# 04_Power.net
KiCad netlist of a schematic drawn in Altium Designer
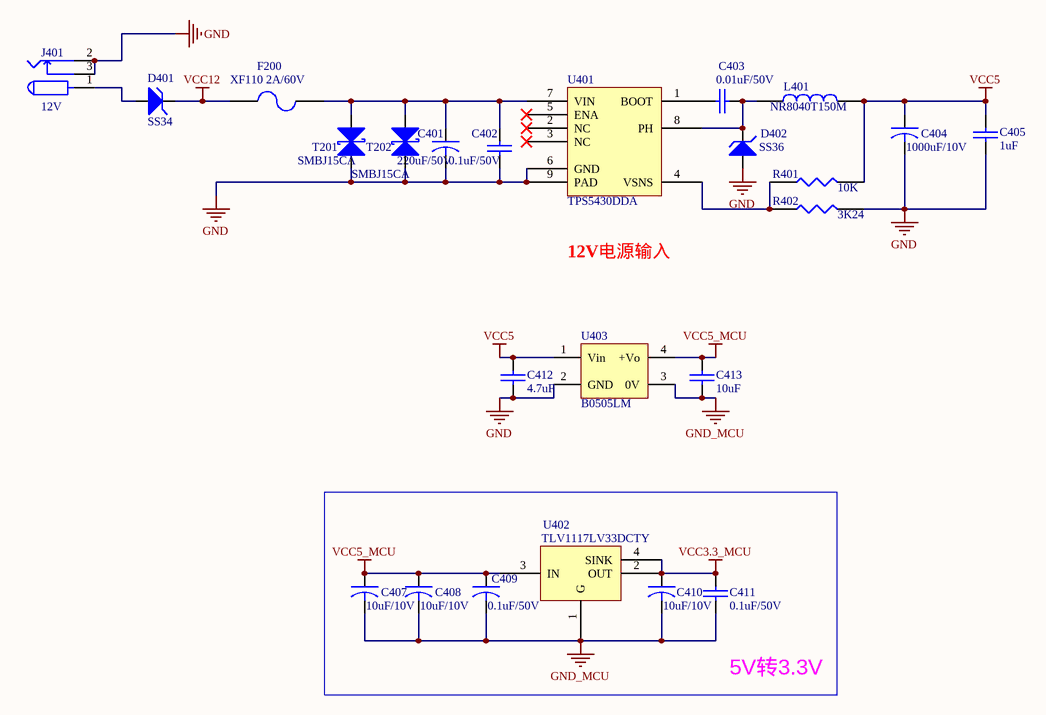
[diagram p0: 04_Power.SchDoc]

(export (version "E")
  (design (tool "Eeschema 10.0.6"))
  (components
    (comp (ref "C401")
      (value "220uF/50V")
      (footprint "CD's_LIB_2018:RB050-100")
      (description "Capacitor")
      (libsource (lib "*") (part "CAPACITOR"))
    )
    (comp (ref "C402")
      (value "0.1uF/50V")
      (footprint "CD's_LIB_2018:0805C")
      (description "Capacitor")
      (libsource (lib "*") (part "CAP"))
    )
    (comp (ref "C403")
      (value "0.01uF/50V")
      (footprint "0603C")
      (description "Capacitor")
      (libsource (lib "*") (part "CAP"))
    )
    (comp (ref "C404")
      (value "1000uF/10V")
      (footprint "RB035-080")
      (description "Capacitor")
      (libsource (lib "*") (part "CAPACITOR"))
    )
    (comp (ref "C405")
      (value "1uF")
      (footprint "0603C")
      (description "Capacitor 0805")
      (libsource (lib "CD's_LIB_2018") (part "0805C"))
    )
    (comp (ref "C407")
      (value "10uF/10V")
      (footprint "0805C")
      (description "Capacitor")
      (libsource (lib "*") (part "CAPACITOR"))
    )
    (comp (ref "C408")
      (value "10uF/10V")
      (footprint "0603C")
      (description "Capacitor")
      (libsource (lib "*") (part "CAPACITOR"))
    )
    (comp (ref "C409")
      (value "0.1uF/50V")
      (footprint "0805C")
      (description "Capacitor")
      (libsource (lib "*") (part "CAPACITOR"))
    )
    (comp (ref "C410")
      (value "10uF/10V")
      (footprint "0805C")
      (description "Capacitor")
      (libsource (lib "*") (part "CAPACITOR"))
    )
    (comp (ref "C411") (value "0.1uF/50V") (footprint "0603C") (libsource (lib "") (part "CAP_1")))
    (comp (ref "C412")
      (value "4.7uF")
      (footprint "0603C")
      (description "Capacitor 0805")
      (libsource (lib "CD's_LIB_2018") (part "0805C"))
    )
    (comp (ref "C413")
      (value "10uF")
      (footprint "0603C")
      (description "Capacitor 0805")
      (libsource (lib "CD's_LIB_2018") (part "0805C"))
    )
    (comp (ref "D401")
      (value "SS34")
      (footprint "D1812")
      (description "Zener Diode")
      (libsource (lib "CD's_LIB_2018") (part "1N5822"))
    )
    (comp (ref "D402")
      (value "SS36")
      (footprint "D1812")
      (description "Zener Diode")
      (libsource (lib "*") (part "SS36"))
    )
    (comp (ref "F200")
      (value "XF110 2A/60V")
      (footprint "FUSE1")
      (description "Fuse")
      (libsource (lib "*") (part "FUSE2"))
    )
    (comp (ref "J401")
      (value "12V")
      (footprint "DC10B")
      (libsource (lib "Explorer STM32F407封装库") (part "POW"))
    )
    (comp (ref "L401") (value "NR8040T150M") (footprint "NR8040") (libsource (lib "*") (part "INDUCTOR")))
    (comp (ref "R401") (value "10K") (footprint "0603R") (libsource (lib "*") (part "RES1")))
    (comp (ref "R402") (value "3K24") (footprint "0603R") (libsource (lib "*") (part "RES1")))
    (comp (ref "T201") (value "SMBJ15CA") (footprint "CD's_LIB_2018:SMBJ") (libsource (lib "*") (part "TVS")))
    (comp (ref "T202") (value "SMBJ15CA") (footprint "CD's_LIB_2018:SMBJ") (libsource (lib "*") (part "TVS")))
    (comp (ref "U401") (value "TPS5430DDA") (footprint "SO-G8") (libsource (lib "*") (part "TPS5430DDA")))
    (comp (ref "U402") (value "TLV1117LV33DCTY") (footprint "SOT-233") (libsource (lib "*") (part "LM1117")))
    (comp (ref "U403")
      (value "B0505LM")
      (footprint "B0505LM")
      (description "DC/DC隔离电源（Mornsun）")
      (libsource (lib "liulei") (part "B0505LM"))
    )
  )
  (nets
    (net (code "1") (name "GND") (class "Default")
      (node (ref "C401") (pin "2") (pinfunction "2_2") (pintype "passive"))
      (node (ref "C402") (pin "2") (pinfunction "2_2") (pintype "passive"))
      (node (ref "C404") (pin "2") (pinfunction "2_2") (pintype "passive"))
      (node (ref "C405") (pin "1") (pinfunction "1_1") (pintype "passive"))
      (node (ref "C412") (pin "2") (pinfunction "2_2") (pintype "passive"))
      (node (ref "D402") (pin "1") (pinfunction "A_1") (pintype "passive"))
      (node (ref "J401") (pin "2") (pintype "passive"))
      (node (ref "J401") (pin "3") (pintype "passive"))
      (node (ref "R402") (pin "2") (pinfunction "2_2") (pintype "passive"))
      (node (ref "T201") (pin "2") (pinfunction "K_2") (pintype "passive"))
      (node (ref "T202") (pin "2") (pinfunction "K_2") (pintype "passive"))
      (node (ref "U401") (pin "6") (pinfunction "GND_6") (pintype "passive"))
      (node (ref "U401") (pin "9") (pinfunction "PAD_9") (pintype "passive"))
      (node (ref "U403") (pin "2") (pinfunction "GND_2") (pintype "passive"))
    )
    (net (code "2") (name "GND_MCU") (class "Default")
      (node (ref "C407") (pin "2") (pinfunction "2_2") (pintype "passive"))
      (node (ref "C408") (pin "2") (pinfunction "2_2") (pintype "passive"))
      (node (ref "C409") (pin "2") (pinfunction "2_2") (pintype "passive"))
      (node (ref "C410") (pin "2") (pinfunction "2_2") (pintype "passive"))
      (node (ref "C411") (pin "2") (pintype "passive"))
      (node (ref "C413") (pin "1") (pinfunction "1_1") (pintype "passive"))
      (node (ref "U402") (pin "1") (pinfunction "G_1") (pintype "passive"))
      (node (ref "U403") (pin "3") (pinfunction "0V_3") (pintype "passive"))
    )
    (net (code "3") (name "Net-(D401-A)") (class "Default")
      (node (ref "D401") (pin "1") (pinfunction "A_1") (pintype "passive"))
      (node (ref "J401") (pin "1") (pintype "passive"))
    )
    (net (code "4") (name "Net-(D402-K)") (class "Default")
      (node (ref "C403") (pin "2") (pinfunction "2_2") (pintype "passive"))
      (node (ref "D402") (pin "2") (pinfunction "K_2") (pintype "passive"))
      (node (ref "L401") (pin "1") (pinfunction "1_1") (pintype "passive"))
      (node (ref "U401") (pin "8") (pinfunction "PH_8") (pintype "passive"))
    )
    (net (code "5") (name "Net-(T201-A)") (class "Default")
      (node (ref "C401") (pin "1") (pinfunction "1_1") (pintype "passive"))
      (node (ref "C402") (pin "1") (pinfunction "1_1") (pintype "passive"))
      (node (ref "F200") (pin "2") (pinfunction "2_2") (pintype "passive"))
      (node (ref "T201") (pin "1") (pinfunction "A_1") (pintype "passive"))
      (node (ref "T202") (pin "1") (pinfunction "A_1") (pintype "passive"))
      (node (ref "U401") (pin "7") (pinfunction "VIN_7") (pintype "passive"))
    )
    (net (code "6") (name "Net-(U401-BOOT)") (class "Default")
      (node (ref "C403") (pin "1") (pinfunction "1_1") (pintype "passive"))
      (node (ref "U401") (pin "1") (pinfunction "BOOT_1") (pintype "passive"))
    )
    (net (code "7") (name "Net-(U401-VSNS)") (class "Default")
      (node (ref "R401") (pin "1") (pinfunction "1_1") (pintype "passive"))
      (node (ref "R402") (pin "1") (pinfunction "1_1") (pintype "passive"))
      (node (ref "U401") (pin "4") (pinfunction "VSNS_4") (pintype "passive"))
    )
    (net (code "8") (name "VCC3.3_MCU") (class "Default")
      (node (ref "C410") (pin "1") (pinfunction "1_1") (pintype "passive"))
      (node (ref "C411") (pin "1") (pintype "passive"))
      (node (ref "U402") (pin "2") (pinfunction "OUT_2") (pintype "passive"))
      (node (ref "U402") (pin "4") (pinfunction "SINK_4") (pintype "passive"))
    )
    (net (code "9") (name "VCC5") (class "Default")
      (node (ref "C404") (pin "1") (pinfunction "1_1") (pintype "passive"))
      (node (ref "C405") (pin "2") (pinfunction "2_2") (pintype "passive"))
      (node (ref "C412") (pin "1") (pinfunction "1_1") (pintype "passive"))
      (node (ref "L401") (pin "2") (pinfunction "2_2") (pintype "passive"))
      (node (ref "R401") (pin "2") (pinfunction "2_2") (pintype "passive"))
      (node (ref "U403") (pin "1") (pinfunction "Vin_1") (pintype "passive"))
    )
    (net (code "10") (name "VCC5_MCU") (class "Default")
      (node (ref "C407") (pin "1") (pinfunction "1_1") (pintype "passive"))
      (node (ref "C408") (pin "1") (pinfunction "1_1") (pintype "passive"))
      (node (ref "C409") (pin "1") (pinfunction "1_1") (pintype "passive"))
      (node (ref "C413") (pin "2") (pinfunction "2_2") (pintype "passive"))
      (node (ref "U402") (pin "3") (pinfunction "IN_3") (pintype "passive"))
      (node (ref "U403") (pin "4") (pinfunction "+Vo_4") (pintype "passive"))
    )
    (net (code "11") (name "VCC12") (class "Default")
      (node (ref "D401") (pin "2") (pinfunction "K_2") (pintype "passive"))
      (node (ref "F200") (pin "1") (pinfunction "1_1") (pintype "passive"))
    )
    (net (code "12") (name "unconnected-(U401-ENA-Pad5)") (class "Default")
      (node (ref "U401") (pin "5") (pinfunction "ENA_5") (pintype "passive+no_connect"))
    )
    (net (code "13") (name "unconnected-(U401-NC-Pad2)") (class "Default")
      (node (ref "U401") (pin "2") (pinfunction "NC_2") (pintype "passive+no_connect"))
    )
    (net (code "14") (name "unconnected-(U401-NC-Pad3)") (class "Default")
      (node (ref "U401") (pin "3") (pinfunction "NC_3") (pintype "passive+no_connect"))
    )
  )
)
